# AUDIO_HEADPHONES_MIC.net
KiCad netlist of a schematic drawn in Altium Designer
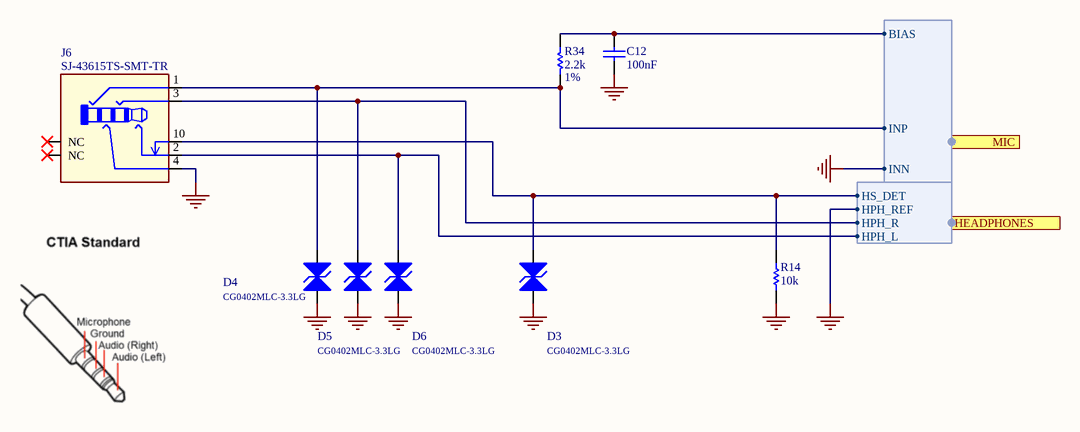
[diagram p0: AUDIO_HEADPHONES_MIC.SchDoc]

(export (version "E")
  (design (tool "Eeschema 10.0.6"))
  (components
    (comp (ref "C12")
      (value "100nF")
      (footprint "CAP-0402")
      (description "CAP CHIP 0402 100nF 10% 50V X5R")
      (fields (field (name "MANUFACTURER") "Murata") (field (name "PART NUMBER") "GRM155R61H104KE19D"))
      (libsource (lib "Clean") (part "CAP"))
    )
    (comp (ref "D3")
      (value "CG0402MLC-3.3LG")
      (footprint "0402")
      (description "DIODE TVS SMD 0402 3.3V ESD PROTECTION")
      (fields (field (name "MANUFACTURER") "Bourns"))
      (libsource (lib "Clean") (part "Diode Bidirectional"))
    )
    (comp (ref "D4")
      (value "CG0402MLC-3.3LG")
      (footprint "0402")
      (description "DIODE TVS SMD 0402 3.3V ESD PROTECTION")
      (fields (field (name "MANUFACTURER") "Bourns"))
      (libsource (lib "Clean") (part "Diode Bidirectional"))
    )
    (comp (ref "D5")
      (value "CG0402MLC-3.3LG")
      (footprint "0402")
      (description "DIODE TVS SMD 0402 3.3V ESD PROTECTION")
      (fields (field (name "MANUFACTURER") "Bourns"))
      (libsource (lib "Clean") (part "Diode Bidirectional"))
    )
    (comp (ref "D6")
      (value "CG0402MLC-3.3LG")
      (footprint "0402")
      (description "DIODE TVS SMD 0402 3.3V ESD PROTECTION")
      (fields (field (name "MANUFACTURER") "Bourns"))
      (libsource (lib "Clean") (part "Diode Bidirectional"))
    )
    (comp (ref "J6")
      (value "SJ-43615TS-SMT-TR")
      (footprint "SJ-43615TS-SMT-TR")
      (description "CONN Audio Jack 3.5mm, 4 conductor, tip switch, SMD mid mount")
      (fields (field (name "MANUFACTURER") "Same Sky"))
      (libsource (lib "Clean") (part "SJ-43615TS-SMT-TR-Symbol-1"))
    )
    (comp (ref "R14")
      (value "10k")
      (footprint "RES-0402")
      (description "RES CHIP 0402 10k 1% 1/16W")
      (fields (field (name "PART NUMBER") "CRCW040210K0FKED") (field (name "MANUFACTURER") "Vishay"))
      (libsource (lib "Clean") (part "RES"))
    )
    (comp (ref "R34")
      (value "2.2k")
      (footprint "RES-0402")
      (description "RES CHIP 0402 2k2 1% 1/16W")
      (fields
        (field (name "MANUFACTURER") "Yageo")
        (field (name "TOLERANCE") "1%")
        (field (name "PART NUMBER") "AF0402FR-072K2L")
      )
      (libsource (lib "Clean") (part "RES"))
    )
  )
  (nets
    (net (code "5") (name "GND") (class "Default")
      (node (ref "C12") (pin "1") (pinfunction "1_1") (pintype "passive"))
      (node (ref "D3") (pin "A") (pinfunction "A_A") (pintype "passive"))
      (node (ref "D4") (pin "A") (pinfunction "A_A") (pintype "passive"))
      (node (ref "D5") (pin "A") (pinfunction "A_A") (pintype "passive"))
      (node (ref "D6") (pin "A") (pinfunction "A_A") (pintype "passive"))
      (node (ref "J6") (pin "4") (pinfunction "4_4") (pintype "passive"))
      (node (ref "R14") (pin "1") (pinfunction "1_1") (pintype "passive"))
    )
    (net (code "6") (name "Net-(C12-Pad2)") (class "Default")
      (node (ref "C12") (pin "2") (pinfunction "2_2") (pintype "passive"))
      (node (ref "R34") (pin "1") (pinfunction "1_1") (pintype "passive"))
    )
    (net (code "7") (name "Net-(D3-PadC)") (class "Default")
      (node (ref "D3") (pin "C") (pinfunction "C_C") (pintype "passive"))
      (node (ref "J6") (pin "10") (pinfunction "10_10") (pintype "passive"))
      (node (ref "R14") (pin "2") (pinfunction "2_2") (pintype "passive"))
    )
    (net (code "8") (name "Net-(D4-PadC)") (class "Default")
      (node (ref "D4") (pin "C") (pinfunction "C_C") (pintype "passive"))
      (node (ref "J6") (pin "1") (pinfunction "1_1") (pintype "passive"))
      (node (ref "R34") (pin "2") (pinfunction "2_2") (pintype "passive"))
    )
    (net (code "9") (name "Net-(D5-PadC)") (class "Default")
      (node (ref "D5") (pin "C") (pinfunction "C_C") (pintype "passive"))
      (node (ref "J6") (pin "3") (pinfunction "3_3") (pintype "passive"))
    )
    (net (code "10") (name "Net-(D6-PadC)") (class "Default")
      (node (ref "D6") (pin "C") (pinfunction "C_C") (pintype "passive"))
      (node (ref "J6") (pin "2") (pinfunction "2_2") (pintype "passive"))
    )
    (net (code "11") (name "unconnected-(J6-NC-Pad11)") (class "Default")
      (node (ref "J6") (pin "11") (pinfunction "NC_11") (pintype "passive+no_connect"))
    )
    (net (code "12") (name "unconnected-(J6-NC-Pad12)") (class "Default")
      (node (ref "J6") (pin "12") (pinfunction "NC_12") (pintype "passive+no_connect"))
    )
  )
)
